# Comparator_Circuit.net
KiCad netlist of a schematic drawn in Altium Designer
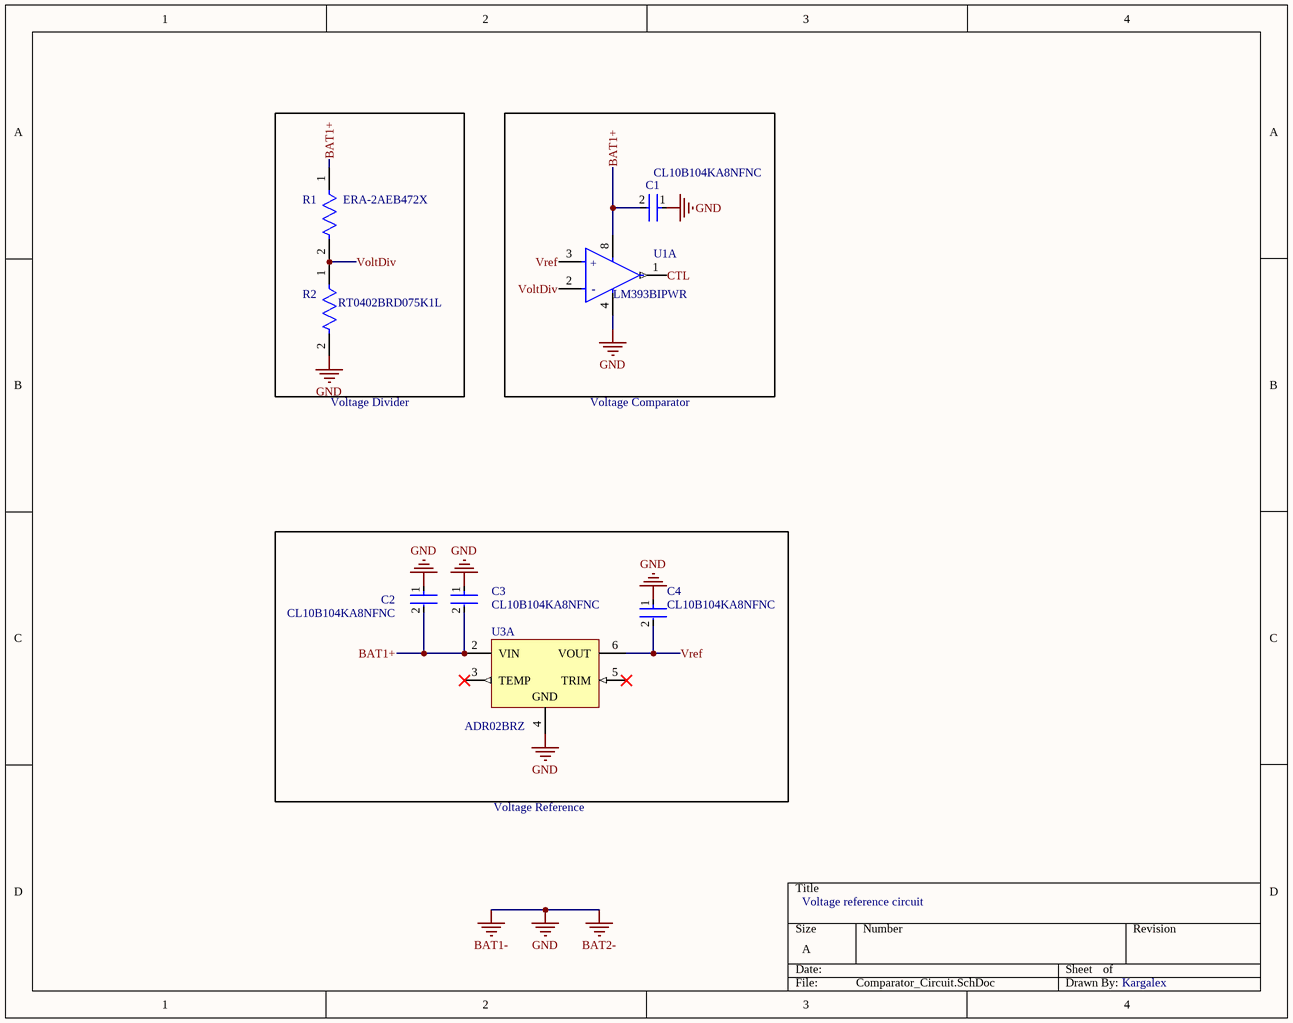
[diagram p0: Comparator_Circuit.SchDoc]

(export (version "E")
  (design (tool "Eeschema 10.0.6"))
  (components
    (comp (ref "C1")
      (value "CL10B104KA8NFNC")
      (footprint "FP-CL10-IPC_C")
      (description "Cap Ceramic 100nF 25V X7R ±10% Pad SMD 0603 +125°C T/R")
      (fields (field (name "TOLERANCE") "10%"))
      (libsource (lib "Altium Content Vault") (part "b4654b650e69147ec39a6b967a45e02"))
    )
    (comp (ref "C2")
      (value "CL10B104KA8NFNC")
      (footprint "FP-CL10-IPC_C")
      (description "Cap Ceramic 100nF 25V X7R ±10% Pad SMD 0603 +125°C T/R")
      (fields (field (name "TOLERANCE") "10%"))
      (libsource (lib "Altium Content Vault") (part "b4654b650e69147ec39a6b967a45e02"))
    )
    (comp (ref "C3")
      (value "CL10B104KA8NFNC")
      (footprint "FP-CL10-IPC_C")
      (description "Cap Ceramic 100nF 25V X7R ±10% Pad SMD 0603 +125°C T/R")
      (fields (field (name "TOLERANCE") "10%"))
      (libsource (lib "Altium Content Vault") (part "b4654b650e69147ec39a6b967a45e02"))
    )
    (comp (ref "C4")
      (value "CL10B104KA8NFNC")
      (footprint "FP-CL10-IPC_C")
      (description "Cap Ceramic 100nF 25V X7R ±10% Pad SMD 0603 +125°C T/R")
      (fields (field (name "TOLERANCE") "10%"))
      (libsource (lib "Altium Content Vault") (part "b4654b650e69147ec39a6b967a45e02"))
    )
    (comp (ref "R1")
      (value "ERA-2AEB472X")
      (footprint "FP-ERA2A-IPC_A")
      (description "RES SMD 4.7K OHM 0.1% 1/16W 0402")
      (fields (field (name "TOLERANCE") "0.1%"))
      (libsource (lib "Altium Content Vault") (part "1029c3af85768c4190bb7ad29bc67b5"))
    )
    (comp (ref "R2")
      (value "RT0402BRD075K1L")
      (footprint "FP-RT0402-MFG")
      (description "RES SMD 5.1K OHM 0.1% 1/16W 0402")
      (fields
        (field (name "OCTOPART") "https://octopart.com/rt0402brd075k1l-yageo-1430932")
        (field (name "MANUFACTURER") "Yageo")
      )
      (libsource (lib "Altium Content Vault") (part "1029c3af85768c4190bb7ad29bc67b5"))
    )
    (comp (ref "U1")
      (value "LM393BIPWR")
      (footprint "FP-PW0008A-MFG")
      (description "Dual Comparators")
      (fields
        (field (name "MANUFACTURER") "Texas Instruments")
        (field (name "OCTOPART") "https://octopart.com/lm393bipwr-texas+instruments-107383910")
      )
      (libsource (lib "Altium Content Vault") (part "d0dfe35d032f86ae96c0c3919f86c94"))
    )
    (comp (ref "U3")
      (value "ADR02BRZ")
      (footprint "ADI-R-8_L")
      (fields (field (name "MANUFACTURER") "Analog Devices"))
      (libsource (lib "Altium Content Vault") (part "ADI-REF0x_ADR0x-X-8"))
    )
  )
  (nets
    (net (code "1") (name "/BAT1+") (class "Default")
      (node (ref "C1") (pin "2") (pinfunction "2_2") (pintype "passive"))
      (node (ref "C2") (pin "2") (pinfunction "2_2") (pintype "passive"))
      (node (ref "C3") (pin "2") (pinfunction "2_2") (pintype "passive"))
      (node (ref "R1") (pin "1") (pinfunction "1_1") (pintype "passive"))
      (node (ref "U1") (pin "8") (pinfunction "VCC_8") (pintype "power_in"))
      (node (ref "U3") (pin "2") (pinfunction "VIN_2") (pintype "power_in"))
    )
    (net (code "2") (name "/CTL") (class "Default")
      (node (ref "U1") (pin "1") (pinfunction "1OUT_1") (pintype "output"))
    )
    (net (code "3") (name "/VoltDiv") (class "Default")
      (node (ref "R1") (pin "2") (pinfunction "2_2") (pintype "passive"))
      (node (ref "R2") (pin "1") (pinfunction "1_1") (pintype "passive"))
      (node (ref "U1") (pin "2") (pinfunction "1IN-_2") (pintype "tri_state"))
    )
    (net (code "4") (name "/Vref") (class "Default")
      (node (ref "C4") (pin "2") (pinfunction "2_2") (pintype "passive"))
      (node (ref "U1") (pin "3") (pinfunction "1IN+_3") (pintype "tri_state"))
      (node (ref "U3") (pin "6") (pinfunction "VOUT_6") (pintype "power_in"))
    )
    (net (code "5") (name "BAT1-") (class "Default")
      (node (ref "C1") (pin "1") (pinfunction "1_1") (pintype "passive"))
      (node (ref "C2") (pin "1") (pinfunction "1_1") (pintype "passive"))
      (node (ref "C3") (pin "1") (pinfunction "1_1") (pintype "passive"))
      (node (ref "C4") (pin "1") (pinfunction "1_1") (pintype "passive"))
      (node (ref "R2") (pin "2") (pinfunction "2_2") (pintype "passive"))
      (node (ref "U1") (pin "4") (pinfunction "GND_4") (pintype "power_in"))
      (node (ref "U3") (pin "4") (pinfunction "GND_4") (pintype "power_in"))
    )
    (net (code "6") (name "unconnected-(U3A-TEMP-Pad3)") (class "Default")
      (node (ref "U3") (pin "3") (pinfunction "TEMP_3") (pintype "output+no_connect"))
    )
    (net (code "7") (name "unconnected-(U3A-TRIM-Pad5)") (class "Default")
      (node (ref "U3") (pin "5") (pinfunction "TRIM_5") (pintype "input+no_connect"))
    )
  )
)
